# SmoothiePanel.net
KiCad netlist of a schematic drawn in EAGLE
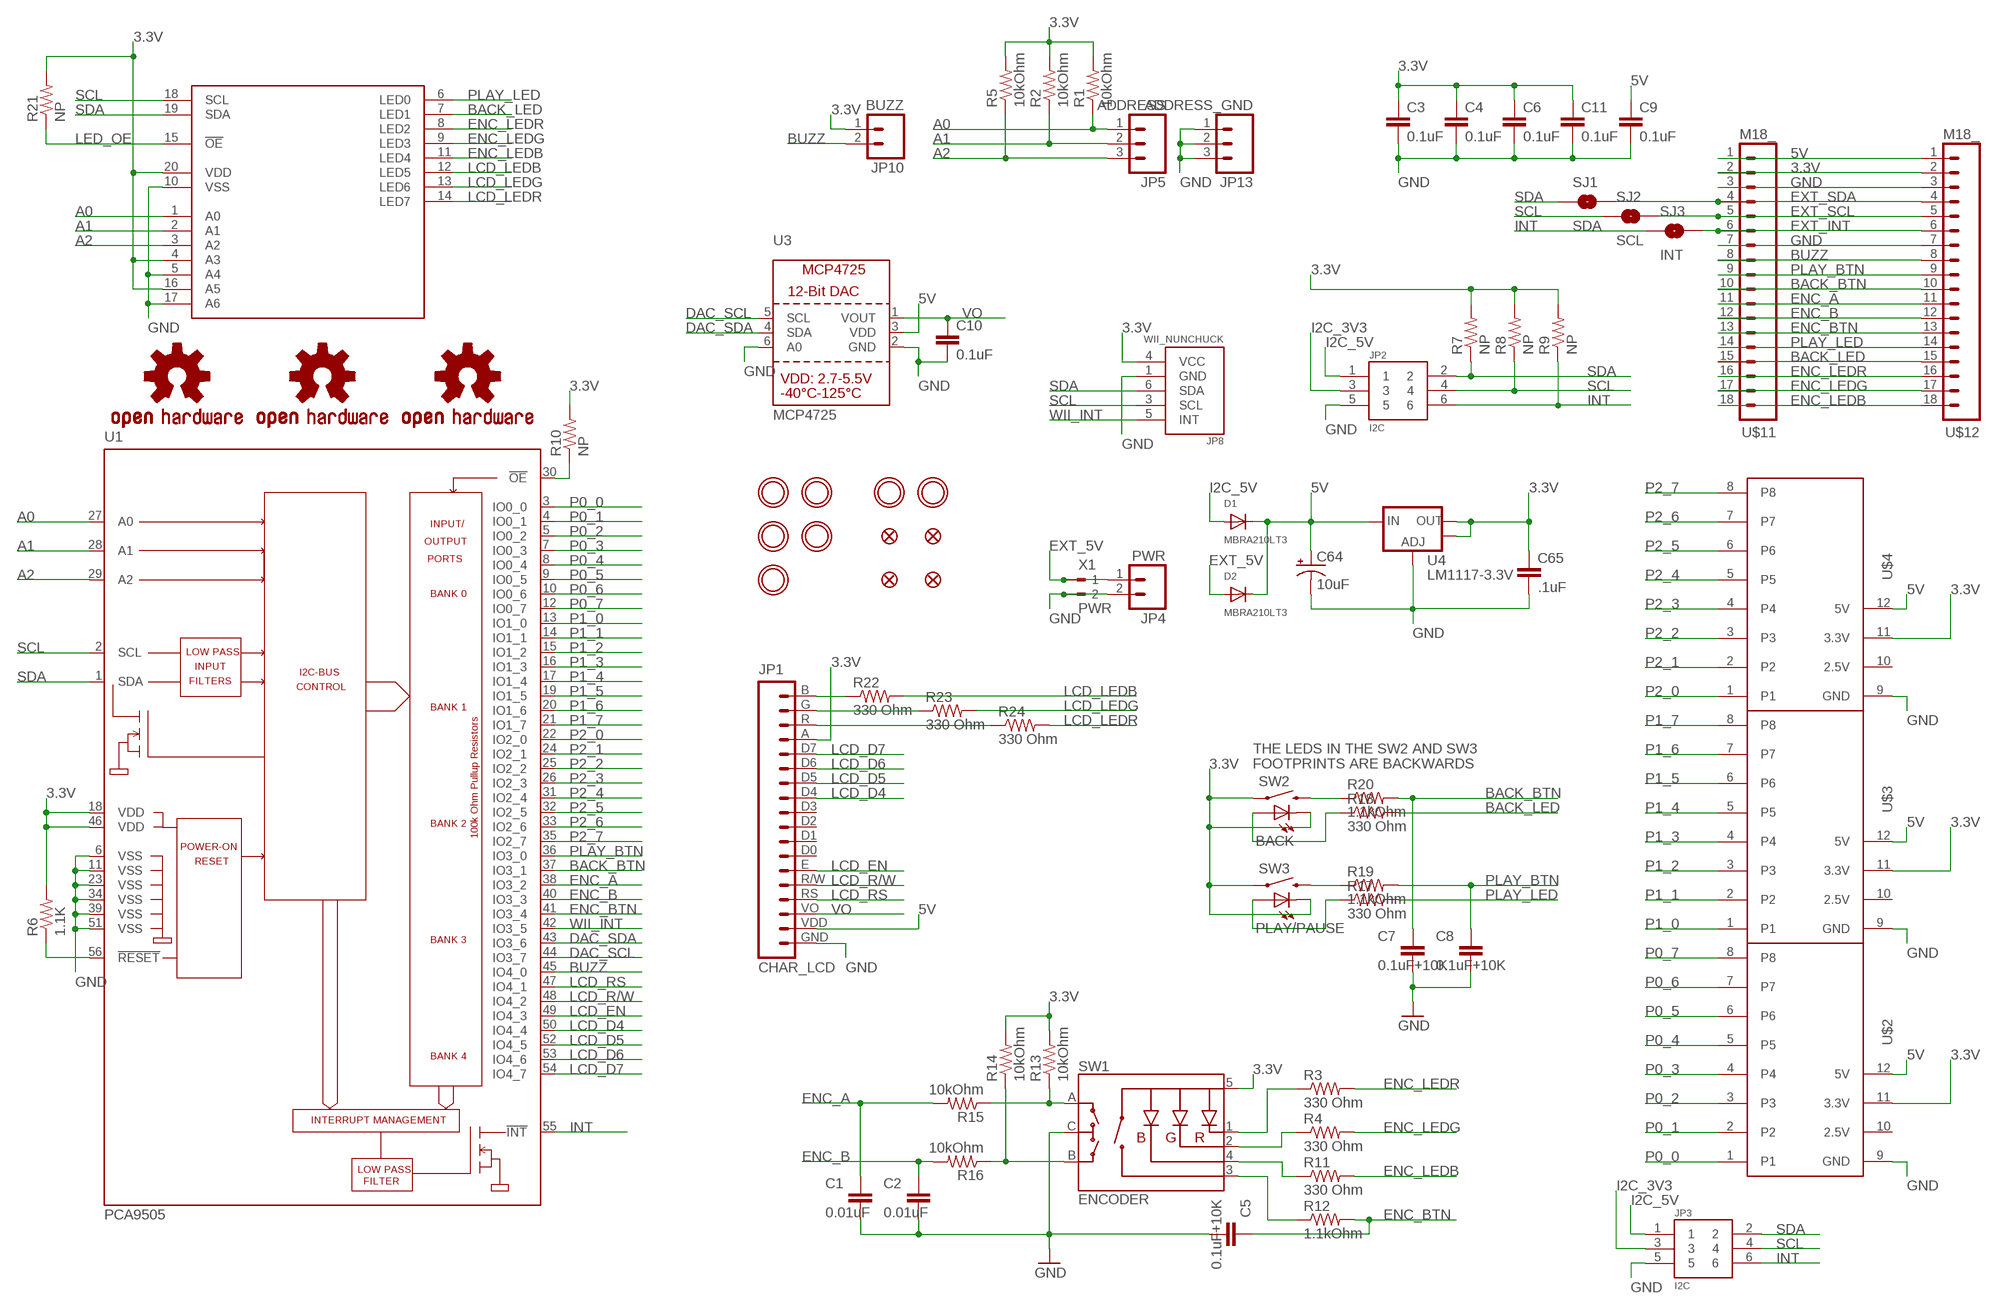
[diagram p0: schematic, sheet 1]

(export (version "E")
  (design (tool "Eeschema 10.0.6"))
  (components
    (comp (ref "C1")
      (value "0.01uF")
      (footprint "eagle-import:C0603")
      (libsource (lib "eagle-import") (part "C-EUC0603"))
    )
    (comp (ref "C2")
      (value "0.01uF")
      (footprint "eagle-import:C0603")
      (libsource (lib "eagle-import") (part "C-EUC0603"))
    )
    (comp (ref "C3")
      (value "0.1uF")
      (footprint "eagle-import:0603-CAP")
      (libsource (lib "eagle-import") (part "CAP0603-CAP"))
    )
    (comp (ref "C4")
      (value "0.1uF")
      (footprint "eagle-import:0603-CAP")
      (libsource (lib "eagle-import") (part "CAP0603-CAP"))
    )
    (comp (ref "C5")
      (value "0.1uF+10K")
      (footprint "eagle-import:C0603")
      (libsource (lib "eagle-import") (part "C-EUC0603"))
    )
    (comp (ref "C6")
      (value "0.1uF")
      (footprint "eagle-import:0603-CAP")
      (libsource (lib "eagle-import") (part "CAP0603-CAP"))
    )
    (comp (ref "C7")
      (value "0.1uF+10K")
      (footprint "eagle-import:C0603")
      (libsource (lib "eagle-import") (part "C-EUC0603"))
    )
    (comp (ref "C8")
      (value "0.1uF+10K")
      (footprint "eagle-import:C0603")
      (libsource (lib "eagle-import") (part "C-EUC0603"))
    )
    (comp (ref "C9")
      (value "0.1uF")
      (footprint "eagle-import:0603-CAP")
      (libsource (lib "eagle-import") (part "CAP0603-CAP"))
    )
    (comp (ref "C10")
      (value "0.1uF")
      (footprint "eagle-import:0603-CAP")
      (libsource (lib "eagle-import") (part "CAP0603-CAP"))
    )
    (comp (ref "C11")
      (value "0.1uF")
      (footprint "eagle-import:0603-CAP")
      (libsource (lib "eagle-import") (part "CAP0603-CAP"))
    )
    (comp (ref "C64")
      (value "10uF")
      (footprint "eagle-import:EIA3216")
      (libsource (lib "eagle-import") (part "CAP_POL1206"))
    )
    (comp (ref "C65")
      (value ".1uF")
      (footprint "eagle-import:C0603")
      (libsource (lib "eagle-import") (part "resistor_C-EUC0603"))
    )
    (comp (ref "D1")
      (value "MBRA210LT3")
      (footprint "eagle-import:SMADIODE")
      (libsource (lib "eagle-import") (part "DIODESMA"))
    )
    (comp (ref "D2")
      (value "MBRA210LT3")
      (footprint "eagle-import:SMADIODE")
      (libsource (lib "eagle-import") (part "DIODESMA"))
    )
    (comp (ref "JP1")
      (value "CHAR_LCD")
      (footprint "eagle-import:TEXT_LCD")
      (libsource (lib "eagle-import") (part "LCD_TEXT"))
    )
    (comp (ref "JP2")
      (value "I2C")
      (footprint "eagle-import:2X3-SHROUDED")
      (libsource (lib "eagle-import") (part "M03X2"))
    )
    (comp (ref "JP3")
      (value "I2C")
      (footprint "eagle-import:2X3-SHROUDED")
      (libsource (lib "eagle-import") (part "M03X2"))
    )
    (comp (ref "JP4")
      (value "PWR")
      (footprint "eagle-import:1X02_LONGPADS")
      (libsource (lib "eagle-import") (part "M02PTH3"))
    )
    (comp (ref "JP5")
      (value "ADDRESS")
      (footprint "eagle-import:1X03")
      (libsource (lib "eagle-import") (part "M03PTH"))
    )
    (comp (ref "JP8")
      (value "WII_NUNCHUCK")
      (footprint "eagle-import:WII_NUNCHUCK")
      (libsource (lib "eagle-import") (part "WII_NUNCHUCK"))
    )
    (comp (ref "JP9")
      (value "FIDUCIAL1X2")
      (footprint "eagle-import:FIDUCIAL-1X2")
      (libsource (lib "eagle-import") (part "FIDUCIAL1X2"))
    )
    (comp (ref "JP10")
      (value "BUZZ")
      (footprint "eagle-import:1X02_XTRA_BIG")
      (libsource (lib "eagle-import") (part "M02PTH4"))
    )
    (comp (ref "JP11")
      (value "FIDUCIAL1X2")
      (footprint "eagle-import:FIDUCIAL-1X2")
      (libsource (lib "eagle-import") (part "FIDUCIAL1X2"))
    )
    (comp (ref "JP12")
      (value "FIDUCIAL1X2")
      (footprint "eagle-import:FIDUCIAL-1X2")
      (libsource (lib "eagle-import") (part "FIDUCIAL1X2"))
    )
    (comp (ref "JP13")
      (value "ADDRESS_GND")
      (footprint "eagle-import:1X03")
      (libsource (lib "eagle-import") (part "M03PTH"))
    )
    (comp (ref "JP14")
      (value "FIDUCIAL1X2")
      (footprint "eagle-import:FIDUCIAL-1X2")
      (libsource (lib "eagle-import") (part "FIDUCIAL1X2"))
    )
    (comp (ref "R1")
      (value "10kOhm")
      (footprint "eagle-import:R0603")
      (libsource (lib "eagle-import") (part "R-US_R0603"))
    )
    (comp (ref "R2")
      (value "10kOhm")
      (footprint "eagle-import:R0603")
      (libsource (lib "eagle-import") (part "R-US_R0603"))
    )
    (comp (ref "R3")
      (value "330 Ohm")
      (footprint "eagle-import:R0603")
      (libsource (lib "eagle-import") (part "R-US_R0603"))
    )
    (comp (ref "R4")
      (value "330 Ohm")
      (footprint "eagle-import:R0603")
      (libsource (lib "eagle-import") (part "R-US_R0603"))
    )
    (comp (ref "R5")
      (value "10kOhm")
      (footprint "eagle-import:R0603")
      (libsource (lib "eagle-import") (part "R-US_R0603"))
    )
    (comp (ref "R6")
      (value "1.1K")
      (footprint "eagle-import:R0603")
      (libsource (lib "eagle-import") (part "R-US_R0603"))
    )
    (comp (ref "R7")
      (value "NP")
      (footprint "eagle-import:R0603")
      (libsource (lib "eagle-import") (part "R-US_R0603"))
    )
    (comp (ref "R8")
      (value "NP")
      (footprint "eagle-import:R0603")
      (libsource (lib "eagle-import") (part "R-US_R0603"))
    )
    (comp (ref "R9")
      (value "NP")
      (footprint "eagle-import:R0603")
      (libsource (lib "eagle-import") (part "R-US_R0603"))
    )
    (comp (ref "R10")
      (value "NP")
      (footprint "eagle-import:R0603")
      (libsource (lib "eagle-import") (part "R-US_R0603"))
    )
    (comp (ref "R11")
      (value "330 Ohm")
      (footprint "eagle-import:R0603")
      (libsource (lib "eagle-import") (part "R-US_R0603"))
    )
    (comp (ref "R12")
      (value "1.1kOhm")
      (footprint "eagle-import:R0603")
      (libsource (lib "eagle-import") (part "R-US_R0603"))
    )
    (comp (ref "R13")
      (value "10kOhm")
      (footprint "eagle-import:R0603")
      (libsource (lib "eagle-import") (part "R-US_R0603"))
    )
    (comp (ref "R14")
      (value "10kOhm")
      (footprint "eagle-import:R0603")
      (libsource (lib "eagle-import") (part "R-US_R0603"))
    )
    (comp (ref "R15")
      (value "10kOhm")
      (footprint "eagle-import:R0603")
      (libsource (lib "eagle-import") (part "R-US_R0603"))
    )
    (comp (ref "R16")
      (value "10kOhm")
      (footprint "eagle-import:R0603")
      (libsource (lib "eagle-import") (part "R-US_R0603"))
    )
    (comp (ref "R17")
      (value "330 Ohm")
      (footprint "eagle-import:R0603")
      (libsource (lib "eagle-import") (part "R-US_R0603"))
    )
    (comp (ref "R18")
      (value "330 Ohm")
      (footprint "eagle-import:R0603")
      (libsource (lib "eagle-import") (part "R-US_R0603"))
    )
    (comp (ref "R19")
      (value "1.1kOhm")
      (footprint "eagle-import:R0603")
      (libsource (lib "eagle-import") (part "R-US_R0603"))
    )
    (comp (ref "R20")
      (value "1.1kOhm")
      (footprint "eagle-import:R0603")
      (libsource (lib "eagle-import") (part "R-US_R0603"))
    )
    (comp (ref "R21")
      (value "NP")
      (footprint "eagle-import:R0603")
      (libsource (lib "eagle-import") (part "R-US_R0603"))
    )
    (comp (ref "R22")
      (value "330 Ohm")
      (footprint "eagle-import:R0603")
      (libsource (lib "eagle-import") (part "R-US_R0603"))
    )
    (comp (ref "R23")
      (value "330 Ohm")
      (footprint "eagle-import:R0603")
      (libsource (lib "eagle-import") (part "R-US_R0603"))
    )
    (comp (ref "R24")
      (value "330 Ohm")
      (footprint "eagle-import:R0603")
      (libsource (lib "eagle-import") (part "R-US_R0603"))
    )
    (comp (ref "SJ1")
      (value "SDA")
      (footprint "eagle-import:SJ_2S-NO")
      (libsource (lib "eagle-import") (part "SOLDERJUMPERNO"))
    )
    (comp (ref "SJ2")
      (value "SCL")
      (footprint "eagle-import:SJ_2S-NO")
      (libsource (lib "eagle-import") (part "SOLDERJUMPERNO"))
    )
    (comp (ref "SJ3")
      (value "INT")
      (footprint "eagle-import:SJ_2S-NO")
      (libsource (lib "eagle-import") (part "SOLDERJUMPERNO"))
    )
    (comp (ref "SW1")
      (value "ENCODER")
      (footprint "eagle-import:ENCODER_LED_3")
      (libsource (lib "eagle-import") (part "ENCODER_RGB_CA"))
    )
    (comp (ref "SW2")
      (value "BACK")
      (footprint "eagle-import:TACTILE-PTH-LED-12MM")
      (libsource (lib "eagle-import") (part "SWITCH-MOMENTARY-LEDPTH"))
    )
    (comp (ref "SW3")
      (value "PLAY/PAUSE")
      (footprint "eagle-import:TACTILE-PTH-LED-12MM")
      (libsource (lib "eagle-import") (part "SWITCH-MOMENTARY-LEDPTH"))
    )
    (comp (ref "U$1")
      (value "OSHW-LOGOL")
      (footprint "eagle-import:OSHW-LOGO-L")
      (libsource (lib "eagle-import") (part "OSHW-LOGOL"))
    )
    (comp (ref "U$2")
      (value "PAPILIO-WING-8BITS")
      (footprint "eagle-import:PAPILIO-WING-8BITS")
      (libsource (lib "eagle-import") (part "PAPILIO-WING-8BITS"))
    )
    (comp (ref "U$3")
      (value "PAPILIO-WING-8BITS")
      (footprint "eagle-import:PAPILIO-WING-8BITS")
      (libsource (lib "eagle-import") (part "PAPILIO-WING-8BITS"))
    )
    (comp (ref "U$4")
      (value "PAPILIO-WING-8BITS")
      (footprint "eagle-import:PAPILIO-WING-8BITS")
      (libsource (lib "eagle-import") (part "PAPILIO-WING-8BITS"))
    )
    (comp (ref "U$5")
      (value "MOUNTINGHOLE3.0THIN")
      (footprint "eagle-import:MOUNTINGHOLE_3.0_PLATEDTHIN")
      (libsource (lib "eagle-import") (part "MOUNTINGHOLE3.0THIN"))
    )
    (comp (ref "U$6")
      (value "MOUNTINGHOLE2.5_THICK")
      (footprint "eagle-import:MOUNTINGHOLE_2.5_PLATED_THICK")
      (libsource (lib "eagle-import") (part "MOUNTINGHOLE2.5_THICK"))
    )
    (comp (ref "U$7")
      (value "MOUNTINGHOLE2.5_THICK")
      (footprint "eagle-import:MOUNTINGHOLE_2.5_PLATED_THICK")
      (libsource (lib "eagle-import") (part "MOUNTINGHOLE2.5_THICK"))
    )
    (comp (ref "U$8")
      (value "OSHW-LOGOL")
      (footprint "eagle-import:OSHW-LOGO-L")
      (libsource (lib "eagle-import") (part "OSHW-LOGOL"))
    )
    (comp (ref "U$9")
      (value "MOUNTINGHOLE3.0THIN")
      (footprint "eagle-import:MOUNTINGHOLE_3.0_PLATEDTHIN")
      (libsource (lib "eagle-import") (part "MOUNTINGHOLE3.0THIN"))
    )
    (comp (ref "U$10")
      (value "OSHW-LOGOL")
      (footprint "eagle-import:OSHW-LOGO-L")
      (libsource (lib "eagle-import") (part "OSHW-LOGOL"))
    )
    (comp (ref "U$11")
      (value "M18_")
      (footprint "eagle-import:1X18")
      (libsource (lib "eagle-import") (part "M18_"))
    )
    (comp (ref "U$12")
      (value "M18_")
      (footprint "eagle-import:1X18")
      (libsource (lib "eagle-import") (part "M18_"))
    )
    (comp (ref "U$13")
      (value "MOUNTINGHOLE3.0THIN")
      (footprint "eagle-import:MOUNTINGHOLE_3.0_PLATEDTHIN")
      (libsource (lib "eagle-import") (part "MOUNTINGHOLE3.0THIN"))
    )
    (comp (ref "U$14")
      (value "MOUNTINGHOLE3.0THIN")
      (footprint "eagle-import:MOUNTINGHOLE_3.0_PLATEDTHIN")
      (libsource (lib "eagle-import") (part "MOUNTINGHOLE3.0THIN"))
    )
    (comp (ref "U$15")
      (value "MOUNTINGHOLE3.0THIN")
      (footprint "eagle-import:MOUNTINGHOLE_3.0_PLATEDTHIN")
      (libsource (lib "eagle-import") (part "MOUNTINGHOLE3.0THIN"))
    )
    (comp (ref "U1")
      (value "PCA9505")
      (footprint "eagle-import:TSSOP56-6")
      (fields (field (name "MPN") "PCA9505DGG,118"))
      (libsource (lib "eagle-import") (part "PCA9505"))
    )
    (comp (ref "U2")
      (value "PCA9634-TSSOP20")
      (footprint "eagle-import:TSSOP20")
      (libsource (lib "eagle-import") (part "PCA9634-TSSOP20"))
    )
    (comp (ref "U3")
      (value "MCP4725")
      (footprint "eagle-import:SOT23-6")
      (libsource (lib "eagle-import") (part "DAC_MCP4725"))
    )
    (comp (ref "U4")
      (value "LM1117-3.3V")
      (footprint "eagle-import:SOT223")
      (libsource (lib "eagle-import") (part "V_REG_LM1117SOT223"))
    )
    (comp (ref "X1")
      (value "PWR")
      (footprint "eagle-import:180-2")
      (libsource (lib "eagle-import") (part "180-2"))
    )
  )
  (nets
    (net (code "1") (name "/3.3V") (class "Default")
      (node (ref "C11") (pin "1") (pinfunction "1_1") (pintype "passive"))
      (node (ref "C3") (pin "1") (pinfunction "1_1") (pintype "passive"))
      (node (ref "C4") (pin "1") (pinfunction "1_1") (pintype "passive"))
      (node (ref "C6") (pin "1") (pinfunction "1_1") (pintype "passive"))
      (node (ref "C65") (pin "1") (pinfunction "1_1") (pintype "passive"))
      (node (ref "JP1") (pin "A") (pinfunction "15_A") (pintype "passive"))
      (node (ref "JP10") (pin "1") (pinfunction "1_1") (pintype "passive"))
      (node (ref "JP8") (pin "4") (pinfunction "VCC_4") (pintype "power_in"))
      (node (ref "R1") (pin "2") (pinfunction "2_2") (pintype "passive"))
      (node (ref "R10") (pin "2") (pinfunction "2_2") (pintype "passive"))
      (node (ref "R13") (pin "2") (pinfunction "2_2") (pintype "passive"))
      (node (ref "R14") (pin "2") (pinfunction "2_2") (pintype "passive"))
      (node (ref "R2") (pin "2") (pinfunction "2_2") (pintype "passive"))
      (node (ref "R21") (pin "2") (pinfunction "2_2") (pintype "passive"))
      (node (ref "R5") (pin "2") (pinfunction "2_2") (pintype "passive"))
      (node (ref "R6") (pin "2") (pinfunction "2_2") (pintype "passive"))
      (node (ref "R7") (pin "2") (pinfunction "2_2") (pintype "passive"))
      (node (ref "R8") (pin "2") (pinfunction "2_2") (pintype "passive"))
      (node (ref "R9") (pin "2") (pinfunction "2_2") (pintype "passive"))
      (node (ref "SW1") (pin "5") (pinfunction "+_5") (pintype "passive"))
      (node (ref "SW2") (pin "4") (pinfunction "1_4") (pintype "passive"))
      (node (ref "SW2") (pin "C") (pinfunction "C_C") (pintype "passive"))
      (node (ref "SW3") (pin "4") (pinfunction "1_4") (pintype "passive"))
      (node (ref "SW3") (pin "C") (pinfunction "C_C") (pintype "passive"))
      (node (ref "U$11") (pin "2") (pinfunction "2_2") (pintype "passive"))
      (node (ref "U$12") (pin "2") (pinfunction "2_2") (pintype "passive"))
      (node (ref "U$2") (pin "11") (pinfunction "3.3V_11") (pintype "bidirectional"))
      (node (ref "U$3") (pin "11") (pinfunction "3.3V_11") (pintype "bidirectional"))
      (node (ref "U$4") (pin "11") (pinfunction "3.3V_11") (pintype "bidirectional"))
      (node (ref "U1") (pin "18") (pinfunction "VDD_18") (pintype "power_in"))
      (node (ref "U1") (pin "46") (pinfunction "VDD_46") (pintype "power_in"))
      (node (ref "U2") (pin "16") (pinfunction "A5_16") (pintype "bidirectional"))
      (node (ref "U2") (pin "20") (pinfunction "VDD_20") (pintype "bidirectional"))
      (node (ref "U2") (pin "4") (pinfunction "A3_4") (pintype "bidirectional"))
      (node (ref "U4") (pin "2") (pinfunction "OUT_2") (pintype "output"))
      (node (ref "U4") (pin "4") (pinfunction "OUT_4") (pintype "output"))
    )
    (net (code "2") (name "/5V") (class "Default")
      (node (ref "C64") (pin "A") (pinfunction "+_A") (pintype "passive"))
      (node (ref "C9") (pin "1") (pinfunction "1_1") (pintype "passive"))
      (node (ref "D1") (pin "C") (pinfunction "C_C") (pintype "passive"))
      (node (ref "D2") (pin "C") (pinfunction "C_C") (pintype "passive"))
      (node (ref "JP1") (pin "VDD") (pinfunction "2_VDD") (pintype "passive"))
      (node (ref "U$11") (pin "1") (pinfunction "1_1") (pintype "passive"))
      (node (ref "U$12") (pin "1") (pinfunction "1_1") (pintype "passive"))
      (node (ref "U$2") (pin "12") (pinfunction "5V_12") (pintype "bidirectional"))
      (node (ref "U$3") (pin "12") (pinfunction "5V_12") (pintype "bidirectional"))
      (node (ref "U$4") (pin "12") (pinfunction "5V_12") (pintype "bidirectional"))
      (node (ref "U3") (pin "3") (pinfunction "VDD_3") (pintype "power_in"))
      (node (ref "U4") (pin "3") (pinfunction "IN_3") (pintype "input"))
    )
    (net (code "3") (name "/A0") (class "Default")
      (node (ref "JP5") (pin "1") (pinfunction "1_1") (pintype "passive"))
      (node (ref "R1") (pin "1") (pinfunction "1_1") (pintype "passive"))
      (node (ref "U1") (pin "27") (pinfunction "A0_27") (pintype "input"))
      (node (ref "U2") (pin "1") (pinfunction "A0_1") (pintype "bidirectional"))
    )
    (net (code "4") (name "/A1") (class "Default")
      (node (ref "JP5") (pin "2") (pinfunction "2_2") (pintype "passive"))
      (node (ref "R2") (pin "1") (pinfunction "1_1") (pintype "passive"))
      (node (ref "U1") (pin "28") (pinfunction "A1_28") (pintype "input"))
      (node (ref "U2") (pin "2") (pinfunction "A1_2") (pintype "bidirectional"))
    )
    (net (code "5") (name "/A2") (class "Default")
      (node (ref "JP5") (pin "3") (pinfunction "3_3") (pintype "passive"))
      (node (ref "R5") (pin "1") (pinfunction "1_1") (pintype "passive"))
      (node (ref "U1") (pin "29") (pinfunction "A2_29") (pintype "input"))
      (node (ref "U2") (pin "3") (pinfunction "A2_3") (pintype "bidirectional"))
    )
    (net (code "6") (name "/BACK_BTN") (class "Default")
      (node (ref "C7") (pin "1") (pinfunction "1_1") (pintype "passive"))
      (node (ref "R20") (pin "2") (pinfunction "2_2") (pintype "passive"))
      (node (ref "U$11") (pin "10") (pinfunction "10_10") (pintype "passive"))
      (node (ref "U$12") (pin "10") (pinfunction "10_10") (pintype "passive"))
      (node (ref "U1") (pin "37") (pinfunction "IO3_1_37") (pintype "bidirectional"))
    )
    (net (code "7") (name "/BACK_LED") (class "Default")
      (node (ref "R18") (pin "2") (pinfunction "2_2") (pintype "passive"))
      (node (ref "U$11") (pin "15") (pinfunction "15_15") (pintype "passive"))
      (node (ref "U$12") (pin "15") (pinfunction "15_15") (pintype "passive"))
      (node (ref "U2") (pin "7") (pinfunction "LED1_7") (pintype "bidirectional"))
    )
    (net (code "8") (name "/BUZZ") (class "Default")
      (node (ref "JP10") (pin "2") (pinfunction "2_2") (pintype "passive"))
      (node (ref "U$11") (pin "8") (pinfunction "8_8") (pintype "passive"))
      (node (ref "U$12") (pin "8") (pinfunction "8_8") (pintype "passive"))
      (node (ref "U1") (pin "45") (pinfunction "IO4_0_45") (pintype "bidirectional"))
    )
    (net (code "9") (name "/DAC_SCL") (class "Default")
      (node (ref "U1") (pin "44") (pinfunction "IO3_7_44") (pintype "bidirectional"))
      (node (ref "U3") (pin "5") (pinfunction "SCL_5") (pintype "bidirectional"))
    )
    (net (code "10") (name "/DAC_SDA") (class "Default")
      (node (ref "U1") (pin "43") (pinfunction "IO3_6_43") (pintype "bidirectional"))
      (node (ref "U3") (pin "4") (pinfunction "SDA_4") (pintype "bidirectional"))
    )
    (net (code "11") (name "/ENC_A") (class "Default")
      (node (ref "C1") (pin "1") (pinfunction "1_1") (pintype "passive"))
      (node (ref "R15") (pin "2") (pinfunction "2_2") (pintype "passive"))
      (node (ref "U$11") (pin "11") (pinfunction "11_11") (pintype "passive"))
      (node (ref "U$12") (pin "11") (pinfunction "11_11") (pintype "passive"))
      (node (ref "U1") (pin "38") (pinfunction "IO3_2_38") (pintype "bidirectional"))
    )
    (net (code "12") (name "/ENC_B") (class "Default")
      (node (ref "C2") (pin "1") (pinfunction "1_1") (pintype "passive"))
      (node (ref "R16") (pin "2") (pinfunction "2_2") (pintype "passive"))
      (node (ref "U$11") (pin "12") (pinfunction "12_12") (pintype "passive"))
      (node (ref "U$12") (pin "12") (pinfunction "12_12") (pintype "passive"))
      (node (ref "U1") (pin "40") (pinfunction "IO3_3_40") (pintype "bidirectional"))
    )
    (net (code "13") (name "/ENC_BTN") (class "Default")
      (node (ref "C5") (pin "1") (pinfunction "1_1") (pintype "passive"))
      (node (ref "R12") (pin "2") (pinfunction "2_2") (pintype "passive"))
      (node (ref "U$11") (pin "13") (pinfunction "13_13") (pintype "passive"))
      (node (ref "U$12") (pin "13") (pinfunction "13_13") (pintype "passive"))
      (node (ref "U1") (pin "41") (pinfunction "IO3_4_41") (pintype "bidirectional"))
    )
    (net (code "14") (name "/ENC_LEDB") (class "Default")
      (node (ref "R11") (pin "2") (pinfunction "2_2") (pintype "passive"))
      (node (ref "U$11") (pin "18") (pinfunction "18_18") (pintype "passive"))
      (node (ref "U$12") (pin "18") (pinfunction "18_18") (pintype "passive"))
      (node (ref "U2") (pin "11") (pinfunction "LED4_11") (pintype "bidirectional"))
    )
    (net (code "15") (name "/ENC_LEDG") (class "Default")
      (node (ref "R4") (pin "2") (pinfunction "2_2") (pintype "passive"))
      (node (ref "U$11") (pin "17") (pinfunction "17_17") (pintype "passive"))
      (node (ref "U$12") (pin "17") (pinfunction "17_17") (pintype "passive"))
      (node (ref "U2") (pin "9") (pinfunction "LED3_9") (pintype "bidirectional"))
    )
    (net (code "16") (name "/ENC_LEDR") (class "Default")
      (node (ref "R3") (pin "2") (pinfunction "2_2") (pintype "passive"))
      (node (ref "U$11") (pin "16") (pinfunction "16_16") (pintype "passive"))
      (node (ref "U$12") (pin "16") (pinfunction "16_16") (pintype "passive"))
      (node (ref "U2") (pin "8") (pinfunction "LED2_8") (pintype "bidirectional"))
    )
    (net (code "17") (name "/EXT_5V") (class "Default")
      (node (ref "D2") (pin "A") (pinfunction "A_A") (pintype "passive"))
      (node (ref "JP4") (pin "1") (pinfunction "1_1") (pintype "passive"))
      (node (ref "X1") (pin "1") (pinfunction "1_1") (pintype "passive"))
    )
    (net (code "18") (name "/EXT_INT") (class "Default")
      (node (ref "SJ3") (pin "2") (pinfunction "2_2") (pintype "passive"))
      (node (ref "U$11") (pin "6") (pinfunction "6_6") (pintype "passive"))
      (node (ref "U$12") (pin "6") (pinfunction "6_6") (pintype "passive"))
    )
    (net (code "19") (name "/EXT_SCL") (class "Default")
      (node (ref "SJ2") (pin "2") (pinfunction "2_2") (pintype "passive"))
      (node (ref "U$11") (pin "5") (pinfunction "5_5") (pintype "passive"))
      (node (ref "U$12") (pin "5") (pinfunction "5_5") (pintype "passive"))
    )
    (net (code "20") (name "/EXT_SDA") (class "Default")
      (node (ref "SJ1") (pin "2") (pinfunction "2_2") (pintype "passive"))
      (node (ref "U$11") (pin "4") (pinfunction "4_4") (pintype "passive"))
      (node (ref "U$12") (pin "4") (pinfunction "4_4") (pintype "passive"))
    )
    (net (code "21") (name "/I2C_3V3") (class "Default")
      (node (ref "JP2") (pin "3") (pinfunction "3_3") (pintype "bidirectional"))
      (node (ref "JP3") (pin "3") (pinfunction "3_3") (pintype "bidirectional"))
    )
    (net (code "22") (name "/I2C_5V") (class "Default")
      (node (ref "D1") (pin "A") (pinfunction "A_A") (pintype "passive"))
      (node (ref "JP2") (pin "1") (pinfunction "1_1") (pintype "bidirectional"))
      (node (ref "JP3") (pin "1") (pinfunction "1_1") (pintype "bidirectional"))
    )
    (net (code "23") (name "/INT") (class "Default")
      (node (ref "JP2") (pin "6") (pinfunction "6_6") (pintype "bidirectional"))
      (node (ref "JP3") (pin "6") (pinfunction "6_6") (pintype "bidirectional"))
      (node (ref "R9") (pin "1") (pinfunction "1_1") (pintype "passive"))
      (node (ref "SJ3") (pin "1") (pinfunction "1_1") (pintype "passive"))
      (node (ref "U1") (pin "55") (pinfunction "~{INT}_55") (pintype "input"))
    )
    (net (code "24") (name "/LCD_D4") (class "Default")
      (node (ref "JP1") (pin "D4") (pinfunction "11_D4") (pintype "passive"))
      (node (ref "U1") (pin "50") (pinfunction "IO4_4_50") (pintype "bidirectional"))
    )
    (net (code "25") (name "/LCD_D5") (class "Default")
      (node (ref "JP1") (pin "D5") (pinfunction "12_D5") (pintype "passive"))
      (node (ref "U1") (pin "52") (pinfunction "IO4_5_52") (pintype "bidirectional"))
    )
    (net (code "26") (name "/LCD_D6") (class "Default")
      (node (ref "JP1") (pin "D6") (pinfunction "13_D6") (pintype "passive"))
      (node (ref "U1") (pin "53") (pinfunction "IO4_6_53") (pintype "bidirectional"))
    )
    (net (code "27") (name "/LCD_D7") (class "Default")
      (node (ref "JP1") (pin "D7") (pinfunction "14_D7") (pintype "passive"))
      (node (ref "U1") (pin "54") (pinfunction "IO4_7_54") (pintype "bidirectional"))
    )
    (net (code "28") (name "/LCD_EN") (class "Default")
      (node (ref "JP1") (pin "E") (pinfunction "6_E") (pintype "passive"))
      (node (ref "U1") (pin "49") (pinfunction "IO4_3_49") (pintype "bidirectional"))
    )
    (net (code "29") (name "/LCD_LEDB") (class "Default")
      (node (ref "R22") (pin "2") (pinfunction "2_2") (pintype "passive"))
      (node (ref "U2") (pin "12") (pinfunction "LED5_12") (pintype "bidirectional"))
    )
    (net (code "30") (name "/LCD_LEDG") (class "Default")
      (node (ref "R23") (pin "2") (pinfunction "2_2") (pintype "passive"))
      (node (ref "U2") (pin "13") (pinfunction "LED6_13") (pintype "bidirectional"))
    )
    (net (code "31") (name "/LCD_LEDR") (class "Default")
      (node (ref "R24") (pin "2") (pinfunction "2_2") (pintype "passive"))
      (node (ref "U2") (pin "14") (pinfunction "LED7_14") (pintype "bidirectional"))
    )
    (net (code "32") (name "/LCD_RS") (class "Default")
      (node (ref "JP1") (pin "RS") (pinfunction "4_RS") (pintype "passive"))
      (node (ref "U1") (pin "47") (pinfunction "IO4_1_47") (pintype "bidirectional"))
    )
    (net (code "33") (name "/LCD_R{slash}W") (class "Default")
      (node (ref "JP1") (pin "R/W") (pinfunction "5_R/W") (pintype "passive"))
      (node (ref "U1") (pin "48") (pinfunction "IO4_2_48") (pintype "bidirectional"))
    )
    (net (code "34") (name "/LED_OE") (class "Default")
      (node (ref "R21") (pin "1") (pinfunction "1_1") (pintype "passive"))
      (node (ref "U2") (pin "15") (pinfunction "~{OE}_15") (pintype "bidirectional"))
    )
    (net (code "35") (name "/P0_0") (class "Default")
      (node (ref "U$2") (pin "1") (pinfunction "P1_1") (pintype "bidirectional"))
      (node (ref "U1") (pin "3") (pinfunction "IO0_0_3") (pintype "bidirectional"))
    )
    (net (code "36") (name "/P0_1") (class "Default")
      (node (ref "U$2") (pin "2") (pinfunction "P2_2") (pintype "bidirectional"))
      (node (ref "U1") (pin "4") (pinfunction "IO0_1_4") (pintype "bidirectional"))
    )
    (net (code "37") (name "/P0_2") (class "Default")
      (node (ref "U$2") (pin "3") (pinfunction "P3_3") (pintype "bidirectional"))
      (node (ref "U1") (pin "5") (pinfunction "IO0_2_5") (pintype "bidirectional"))
    )
    (net (code "38") (name "/P0_3") (class "Default")
      (node (ref "U$2") (pin "4") (pinfunction "P4_4") (pintype "bidirectional"))
      (node (ref "U1") (pin "7") (pinfunction "IO0_3_7") (pintype "bidirectional"))
    )
    (net (code "39") (name "/P0_4") (class "Default")
      (node (ref "U$2") (pin "5") (pinfunction "P5_5") (pintype "bidirectional"))
      (node (ref "U1") (pin "8") (pinfunction "IO0_4_8") (pintype "bidirectional"))
    )
    (net (code "40") (name "/P0_5") (class "Default")
      (node (ref "U$2") (pin "6") (pinfunction "P6_6") (pintype "bidirectional"))
      (node (ref "U1") (pin "9") (pinfunction "IO0_5_9") (pintype "bidirectional"))
    )
    (net (code "41") (name "/P0_6") (class "Default")
      (node (ref "U$2") (pin "7") (pinfunction "P7_7") (pintype "bidirectional"))
      (node (ref "U1") (pin "10") (pinfunction "IO0_6_10") (pintype "bidirectional"))
    )
    (net (code "42") (name "/P0_7") (class "Default")
      (node (ref "U$2") (pin "8") (pinfunction "P8_8") (pintype "bidirectional"))
      (node (ref "U1") (pin "12") (pinfunction "IO0_7_12") (pintype "bidirectional"))
    )
    (net (code "43") (name "/P1_0") (class "Default")
      (node (ref "U$3") (pin "1") (pinfunction "P1_1") (pintype "bidirectional"))
      (node (ref "U1") (pin "13") (pinfunction "IO1_0_13") (pintype "bidirectional"))
    )
    (net (code "44") (name "/P1_1") (class "Default")
      (node (ref "U$3") (pin "2") (pinfunction "P2_2") (pintype "bidirectional"))
      (node (ref "U1") (pin "14") (pinfunction "IO1_1_14") (pintype "bidirectional"))
    )
    (net (code "45") (name "/P1_2") (class "Default")
      (node (ref "U$3") (pin "3") (pinfunction "P3_3") (pintype "bidirectional"))
      (node (ref "U1") (pin "15") (pinfunction "IO1_2_15") (pintype "bidirectional"))
    )
    (net (code "46") (name "/P1_3") (class "Default")
      (node (ref "U$3") (pin "4") (pinfunction "P4_4") (pintype "bidirectional"))
      (node (ref "U1") (pin "16") (pinfunction "IO1_3_16") (pintype "bidirectional"))
    )
    (net (code "47") (name "/P1_4") (class "Default")
      (node (ref "U$3") (pin "5") (pinfunction "P5_5") (pintype "bidirectional"))
      (node (ref "U1") (pin "17") (pinfunction "IO1_4_17") (pintype "bidirectional"))
    )
    (net (code "48") (name "/P1_5") (class "Default")
      (node (ref "U$3") (pin "6") (pinfunction "P6_6") (pintype "bidirectional"))
      (node (ref "U1") (pin "19") (pinfunction "IO1_5_19") (pintype "bidirectional"))
    )
    (net (code "49") (name "/P1_6") (class "Default")
      (node (ref "U$3") (pin "7") (pinfunction "P7_7") (pintype "bidirectional"))
      (node (ref "U1") (pin "20") (pinfunction "IO1_6_20") (pintype "bidirectional"))
    )
    (net (code "50") (name "/P1_7") (class "Default")
      (node (ref "U$3") (pin "8") (pinfunction "P8_8") (pintype "bidirectional"))
      (node (ref "U1") (pin "21") (pinfunction "IO1_7_21") (pintype "bidirectional"))
    )
    (net (code "51") (name "/P2_0") (class "Default")
      (node (ref "U$4") (pin "1") (pinfunction "P1_1") (pintype "bidirectional"))
      (node (ref "U1") (pin "22") (pinfunction "IO2_0_22") (pintype "bidirectional"))
    )
    (net (code "52") (name "/P2_1") (class "Default")
      (node (ref "U$4") (pin "2") (pinfunction "P2_2") (pintype "bidirectional"))
      (node (ref "U1") (pin "24") (pinfunction "IO2_1_24") (pintype "bidirectional"))
    )
    (net (code "53") (name "/P2_2") (class "Default")
      (node (ref "U$4") (pin "3") (pinfunction "P3_3") (pintype "bidirectional"))
      (node (ref "U1") (pin "25") (pinfunction "IO2_2_25") (pintype "bidirectional"))
    )
    (net (code "54") (name "/P2_3") (class "Default")
      (node (ref "U$4") (pin "4") (pinfunction "P4_4") (pintype "bidirectional"))
      (node (ref "U1") (pin "26") (pinfunction "IO2_3_26") (pintype "bidirectional"))
    )
    (net (code "55") (name "/P2_4") (class "Default")
      (node (ref "U$4") (pin "5") (pinfunction "P5_5") (pintype "bidirectional"))
      (node (ref "U1") (pin "31") (pinfunction "IO2_4_31") (pintype "bidirectional"))
    )
    (net (code "56") (name "/P2_5") (class "Default")
      (node (ref "U$4") (pin "6") (pinfunction "P6_6") (pintype "bidirectional"))
      (node (ref "U1") (pin "32") (pinfunction "IO2_5_32") (pintype "bidirectional"))
    )
    (net (code "57") (name "/P2_6") (class "Default")
      (node (ref "U$4") (pin "7") (pinfunction "P7_7") (pintype "bidirectional"))
      (node (ref "U1") (pin "33") (pinfunction "IO2_6_33") (pintype "bidirectional"))
    )
    (net (code "58") (name "/P2_7") (class "Default")
      (node (ref "U$4") (pin "8") (pinfunction "P8_8") (pintype "bidirectional"))
      (node (ref "U1") (pin "35") (pinfunction "IO2_7_35") (pintype "bidirectional"))
    )
    (net (code "59") (name "/PLAY_BTN") (class "Default")
      (node (ref "C8") (pin "1") (pinfunction "1_1") (pintype "passive"))
      (node (ref "R19") (pin "2") (pinfunction "2_2") (pintype "passive"))
      (node (ref "U$11") (pin "9") (pinfunction "9_9") (pintype "passive"))
      (node (ref "U$12") (pin "9") (pinfunction "9_9") (pintype "passive"))
      (node (ref "U1") (pin "36") (pinfunction "IO3_0_36") (pintype "bidirectional"))
    )
    (net (code "60") (name "/PLAY_LED") (class "Default")
      (node (ref "R17") (pin "2") (pinfunction "2_2") (pintype "passive"))
      (node (ref "U$11") (pin "14") (pinfunction "14_14") (pintype "passive"))
      (node (ref "U$12") (pin "14") (pinfunction "14_14") (pintype "passive"))
      (node (ref "U2") (pin "6") (pinfunction "LED0_6") (pintype "bidirectional"))
    )
    (net (code "61") (name "/SCL") (class "Default")
      (node (ref "JP2") (pin "4") (pinfunction "4_4") (pintype "bidirectional"))
      (node (ref "JP3") (pin "4") (pinfunction "4_4") (pintype "bidirectional"))
      (node (ref "JP8") (pin "3") (pinfunction "SCL_3") (pintype "bidirectional"))
      (node (ref "R8") (pin "1") (pinfunction "1_1") (pintype "passive"))
      (node (ref "SJ2") (pin "1") (pinfunction "1_1") (pintype "passive"))
      (node (ref "U1") (pin "2") (pinfunction "SCL_2") (pintype "input"))
      (node (ref "U2") (pin "18") (pinfunction "SCL_18") (pintype "bidirectional"))
    )
    (net (code "62") (name "/SDA") (class "Default")
      (node (ref "JP2") (pin "2") (pinfunction "2_2") (pintype "bidirectional"))
      (node (ref "JP3") (pin "2") (pinfunction "2_2") (pintype "bidirectional"))
      (node (ref "JP8") (pin "6") (pinfunction "SDA_6") (pintype "bidirectional"))
      (node (ref "R7") (pin "1") (pinfunction "1_1") (pintype "passive"))
      (node (ref "SJ1") (pin "1") (pinfunction "1_1") (pintype "passive"))
      (node (ref "U1") (pin "1") (pinfunction "SDA_1") (pintype "bidirectional"))
      (node (ref "U2") (pin "19") (pinfunction "SDA_19") (pintype "bidirectional"))
    )
    (net (code "63") (name "/VO") (class "Default")
      (node (ref "C10") (pin "1") (pinfunction "1_1") (pintype "passive"))
      (node (ref "JP1") (pin "VO") (pinfunction "3_VO") (pintype "passive"))
      (node (ref "U3") (pin "1") (pinfunction "VOUT_1") (pintype "output"))
    )
    (net (code "64") (name "/WII_INT") (class "Default")
      (node (ref "JP8") (pin "5") (pinfunction "INT_5") (pintype "bidirectional"))
      (node (ref "U1") (pin "42") (pinfunction "IO3_5_42") (pintype "bidirectional"))
    )
    (net (code "65") (name "GND") (class "Default")
      (node (ref "C1") (pin "2") (pinfunction "2_2") (pintype "passive"))
      (node (ref "C10") (pin "2") (pinfunction "2_2") (pintype "passive"))
      (node (ref "C11") (pin "2") (pinfunction "2_2") (pintype "passive"))
      (node (ref "C2") (pin "2") (pinfunction "2_2") (pintype "passive"))
      (node (ref "C3") (pin "2") (pinfunction "2_2") (pintype "passive"))
      (node (ref "C4") (pin "2") (pinfunction "2_2") (pintype "passive"))
      (node (ref "C5") (pin "2") (pinfunction "2_2") (pintype "passive"))
      (node (ref "C6") (pin "2") (pinfunction "2_2") (pintype "passive"))
      (node (ref "C64") (pin "C") (pinfunction "-_C") (pintype "passive"))
      (node (ref "C65") (pin "2") (pinfunction "2_2") (pintype "passive"))
      (node (ref "C7") (pin "2") (pinfunction "2_2") (pintype "passive"))
      (node (ref "C8") (pin "2") (pinfunction "2_2") (pintype "passive"))
      (node (ref "C9") (pin "2") (pinfunction "2_2") (pintype "passive"))
      (node (ref "JP1") (pin "GND") (pinfunction "1_GND") (pintype "passive"))
      (node (ref "JP13") (pin "1") (pinfunction "1_1") (pintype "passive"))
      (node (ref "JP13") (pin "2") (pinfunction "2_2") (pintype "passive"))
      (node (ref "JP13") (pin "3") (pinfunction "3_3") (pintype "passive"))
      (node (ref "JP2") (pin "5") (pinfunction "5_5") (pintype "bidirectional"))
      (node (ref "JP3") (pin "5") (pinfunction "5_5") (pintype "bidirectional"))
      (node (ref "JP4") (pin "2") (pinfunction "2_2") (pintype "passive"))
      (node (ref "JP8") (pin "1") (pinfunction "GND_1") (pintype "power_in"))
      (node (ref "SW1") (pin "C") (pinfunction "C_C") (pintype "bidirectional"))
      (node (ref "U$11") (pin "3") (pinfunction "3_3") (pintype "passive"))
      (node (ref "U$11") (pin "7") (pinfunction "7_7") (pintype "passive"))
      (node (ref "U$12") (pin "3") (pinfunction "3_3") (pintype "passive"))
      (node (ref "U$12") (pin "7") (pinfunction "7_7") (pintype "passive"))
      (node (ref "U$2") (pin "9") (pinfunction "GND_9") (pintype "bidirectional"))
      (node (ref "U$3") (pin "9") (pinfunction "GND_9") (pintype "bidirectional"))
      (node (ref "U$4") (pin "9") (pinfunction "GND_9") (pintype "bidirectional"))
      (node (ref "U1") (pin "11") (pinfunction "VSS_11") (pintype "power_in"))
      (node (ref "U1") (pin "23") (pinfunction "VSS_23") (pintype "power_in"))
      (node (ref "U1") (pin "34") (pinfunction "VSS_34") (pintype "power_in"))
      (node (ref "U1") (pin "39") (pinfunction "VSS_39") (pintype "power_in"))
      (node (ref "U1") (pin "51") (pinfunction "VSS_51") (pintype "power_in"))
      (node (ref "U1") (pin "6") (pinfunction "VSS_6") (pintype "power_in"))
      (node (ref "U2") (pin "10") (pinfunction "VSS_10") (pintype "bidirectional"))
      (node (ref "U2") (pin "17") (pinfunction "A6_17") (pintype "bidirectional"))
      (node (ref "U2") (pin "5") (pinfunction "A4_5") (pintype "bidirectional"))
      (node (ref "U3") (pin "2") (pinfunction "GND_2") (pintype "power_in"))
      (node (ref "U3") (pin "6") (pinfunction "A0_6") (pintype "input"))
      (node (ref "U4") (pin "1") (pinfunction "ADJ_1") (pintype "input"))
      (node (ref "X1") (pin "2") (pinfunction "2_2") (pintype "passive"))
    )
    (net (code "66") (name "Net-(JP1-16)") (class "Default")
      (node (ref "JP1") (pin "R") (pinfunction "16_R") (pintype "passive"))
      (node (ref "R24") (pin "1") (pinfunction "1_1") (pintype "passive"))
    )
    (net (code "67") (name "Net-(JP1-17)") (class "Default")
      (node (ref "JP1") (pin "G") (pinfunction "17_G") (pintype "passive"))
      (node (ref "R23") (pin "1") (pinfunction "1_1") (pintype "passive"))
    )
    (net (code "68") (name "Net-(JP1-18)") (class "Default")
      (node (ref "JP1") (pin "B") (pinfunction "18_B") (pintype "passive"))
      (node (ref "R22") (pin "1") (pinfunction "1_1") (pintype "passive"))
    )
    (net (code "69") (name "Net-(R13-Pad1)") (class "Default")
      (node (ref "R13") (pin "1") (pinfunction "1_1") (pintype "passive"))
      (node (ref "R15") (pin "1") (pinfunction "1_1") (pintype "passive"))
      (node (ref "SW1") (pin "A") (pinfunction "A_A") (pintype "bidirectional"))
    )
    (net (code "70") (name "Net-(R14-Pad1)") (class "Default")
      (node (ref "R14") (pin "1") (pinfunction "1_1") (pintype "passive"))
      (node (ref "R16") (pin "1") (pinfunction "1_1") (pintype "passive"))
      (node (ref "SW1") (pin "B") (pinfunction "B_B") (pintype "bidirectional"))
    )
    (net (code "71") (name "Net-(R17-Pad1)") (class "Default")
      (node (ref "R17") (pin "1") (pinfunction "1_1") (pintype "passive"))
      (node (ref "SW3") (pin "A") (pinfunction "A_A") (pintype "passive"))
    )
    (net (code "72") (name "Net-(R18-Pad1)") (class "Default")
      (node (ref "R18") (pin "1") (pinfunction "1_1") (pintype "passive"))
      (node (ref "SW2") (pin "A") (pinfunction "A_A") (pintype "passive"))
    )
    (net (code "73") (name "Net-(R19-Pad1)") (class "Default")
      (node (ref "R19") (pin "1") (pinfunction "1_1") (pintype "passive"))
      (node (ref "SW3") (pin "2") (pinfunction "2_2") (pintype "passive"))
    )
    (net (code "74") (name "Net-(R20-Pad1)") (class "Default")
      (node (ref "R20") (pin "1") (pinfunction "1_1") (pintype "passive"))
      (node (ref "SW2") (pin "2") (pinfunction "2_2") (pintype "passive"))
    )
    (net (code "75") (name "Net-(SW1--B)") (class "Default")
      (node (ref "R11") (pin "1") (pinfunction "1_1") (pintype "passive"))
      (node (ref "SW1") (pin "4") (pinfunction "-B_4") (pintype "passive"))
    )
    (net (code "76") (name "Net-(SW1--G)") (class "Default")
      (node (ref "R4") (pin "1") (pinfunction "1_1") (pintype "passive"))
      (node (ref "SW1") (pin "2") (pinfunction "-G_2") (pintype "passive"))
    )
    (net (code "77") (name "Net-(SW1--R)") (class "Default")
      (node (ref "R3") (pin "1") (pinfunction "1_1") (pintype "passive"))
      (node (ref "SW1") (pin "1") (pinfunction "-R_1") (pintype "passive"))
    )
    (net (code "78") (name "Net-(SW1-SW)") (class "Default")
      (node (ref "R12") (pin "1") (pinfunction "1_1") (pintype "passive"))
      (node (ref "SW1") (pin "3") (pinfunction "SW_3") (pintype "passive"))
    )
    (net (code "79") (name "Net-(U1-~{OE})") (class "Default")
      (node (ref "R10") (pin "1") (pinfunction "1_1") (pintype "passive"))
      (node (ref "U1") (pin "30") (pinfunction "~{OE}_30") (pintype "input"))
    )
    (net (code "80") (name "Net-(U1-~{RESET})") (class "Default")
      (node (ref "R6") (pin "1") (pinfunction "1_1") (pintype "passive"))
      (node (ref "U1") (pin "56") (pinfunction "~{RESET}_56") (pintype "input"))
    )
    (net (code "81") (name "unconnected-(JP1-7-PadD0)") (class "Default")
      (node (ref "JP1") (pin "D0") (pinfunction "7_D0") (pintype "passive"))
    )
    (net (code "82") (name "unconnected-(JP1-8-PadD1)") (class "Default")
      (node (ref "JP1") (pin "D1") (pinfunction "8_D1") (pintype "passive"))
    )
    (net (code "83") (name "unconnected-(JP1-9-PadD2)") (class "Default")
      (node (ref "JP1") (pin "D2") (pinfunction "9_D2") (pintype "passive"))
    )
    (net (code "84") (name "unconnected-(JP1-10-PadD3)") (class "Default")
      (node (ref "JP1") (pin "D3") (pinfunction "10_D3") (pintype "passive"))
    )
    (net (code "85") (name "unconnected-(U$2-2.5V-Pad10)") (class "Default")
      (node (ref "U$2") (pin "10") (pinfunction "2.5V_10") (pintype "bidirectional"))
    )
    (net (code "86") (name "unconnected-(U$3-2.5V-Pad10)") (class "Default")
      (node (ref "U$3") (pin "10") (pinfunction "2.5V_10") (pintype "bidirectional"))
    )
    (net (code "87") (name "unconnected-(U$4-2.5V-Pad10)") (class "Default")
      (node (ref "U$4") (pin "10") (pinfunction "2.5V_10") (pintype "bidirectional"))
    )
  )
)
